# Switch.net
KiCad netlist of a schematic drawn in Altium Designer
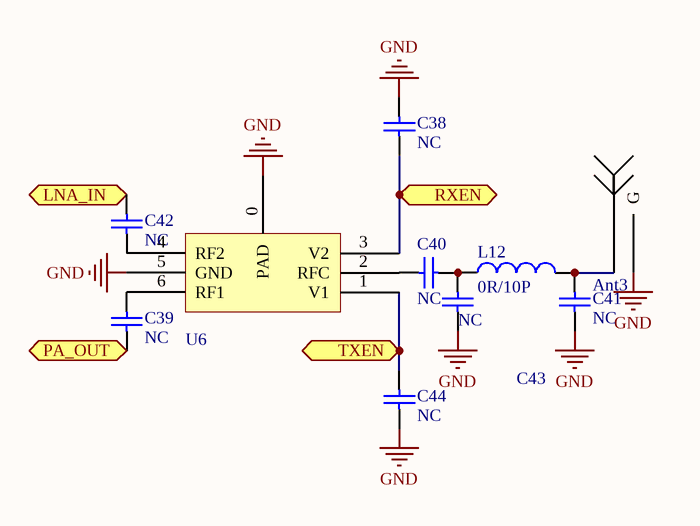
[diagram p0: Switch.SchDoc]

(export (version "E")
  (design (tool "Eeschema 10.0.6"))
  (components
    (comp (ref "Ant3") (value "Antenna") (footprint "SMA") (libsource (lib "RTC6705") (part "Antenna")))
    (comp (ref "C38")
      (value "NC")
      (footprint "0402")
      (description "Capacitor")
      (fields (field (name "Comment") "Cap") (field (name "PUBLISHER") "Altium Limited"))
      (libsource (lib "RTC6705") (part "Cap"))
    )
    (comp (ref "C39")
      (value "NC")
      (footprint "0402")
      (description "Capacitor")
      (fields (field (name "Comment") "Cap") (field (name "PUBLISHER") "Altium Limited"))
      (libsource (lib "RTC6705") (part "Cap"))
    )
    (comp (ref "C40")
      (value "NC")
      (footprint "0402")
      (description "Capacitor")
      (fields (field (name "Comment") "Cap") (field (name "PUBLISHER") "Altium Limited"))
      (libsource (lib "RTC6705") (part "Cap"))
    )
    (comp (ref "C41")
      (value "NC")
      (footprint "0402")
      (description "Capacitor")
      (fields (field (name "Comment") "Cap") (field (name "PUBLISHER") "Altium Limited"))
      (libsource (lib "RTC6705") (part "Cap"))
    )
    (comp (ref "C42")
      (value "NC")
      (footprint "0402")
      (description "Capacitor")
      (fields (field (name "Comment") "Cap") (field (name "PUBLISHER") "Altium Limited"))
      (libsource (lib "RTC6705") (part "Cap"))
    )
    (comp (ref "C43")
      (value "NC")
      (footprint "0402")
      (description "Capacitor")
      (fields (field (name "Comment") "Cap") (field (name "PUBLISHER") "Altium Limited"))
      (libsource (lib "RTC6705") (part "Cap"))
    )
    (comp (ref "C44")
      (value "NC")
      (footprint "0402")
      (description "Capacitor")
      (fields (field (name "Comment") "Cap") (field (name "PUBLISHER") "Altium Limited"))
      (libsource (lib "RTC6705") (part "Cap"))
    )
    (comp (ref "L12")
      (value "0R/10P")
      (footprint "0402")
      (description "Inductor")
      (fields (field (name "PUBLISHER") "Altium Limited"))
      (libsource (lib "Miscellaneous Devices") (part "Inductor"))
    )
    (comp (ref "U6")
      (value "SKY13370-374LF")
      (footprint "SKY65404-31")
      (libsource (lib "BK5811") (part "SKY13370-374LF"))
    )
  )
  (nets
    (net (code "1") (name "/LNA_IN") (class "Default")
      (node (ref "C42") (pin "2") (pinfunction "2_2") (pintype "passive"))
    )
    (net (code "2") (name "/PA_OUT") (class "Default")
      (node (ref "C39") (pin "1") (pinfunction "1_1") (pintype "passive"))
    )
    (net (code "3") (name "/RXEN") (class "Default")
      (node (ref "C38") (pin "2") (pinfunction "2_2") (pintype "passive"))
      (node (ref "U6") (pin "3") (pinfunction "V2_3") (pintype "passive"))
    )
    (net (code "4") (name "/TXEN") (class "Default")
      (node (ref "C44") (pin "2") (pinfunction "2_2") (pintype "passive"))
      (node (ref "U6") (pin "1") (pinfunction "V1_1") (pintype "passive"))
    )
    (net (code "5") (name "GND") (class "Default")
      (node (ref "Ant3") (pin "GND") (pinfunction "G_GND") (pintype "passive"))
      (node (ref "C38") (pin "1") (pinfunction "1_1") (pintype "passive"))
      (node (ref "C41") (pin "2") (pinfunction "2_2") (pintype "passive"))
      (node (ref "C43") (pin "2") (pinfunction "2_2") (pintype "passive"))
      (node (ref "C44") (pin "1") (pinfunction "1_1") (pintype "passive"))
      (node (ref "U6") (pin "0") (pinfunction "PAD_0") (pintype "passive"))
      (node (ref "U6") (pin "5") (pinfunction "GND_5") (pintype "passive"))
    )
    (net (code "6") (name "Net-(Ant3-Pad1)") (class "Default")
      (node (ref "Ant3") (pin "1") (pinfunction "1_1") (pintype "passive"))
      (node (ref "C41") (pin "1") (pinfunction "1_1") (pintype "passive"))
      (node (ref "L12") (pin "2") (pinfunction "2_2") (pintype "passive"))
    )
    (net (code "7") (name "Net-(C40-Pad2)") (class "Default")
      (node (ref "C40") (pin "2") (pinfunction "2_2") (pintype "passive"))
      (node (ref "C43") (pin "1") (pinfunction "1_1") (pintype "passive"))
      (node (ref "L12") (pin "1") (pinfunction "1_1") (pintype "passive"))
    )
    (net (code "8") (name "Net-(U6-RF1)") (class "Default")
      (node (ref "C39") (pin "2") (pinfunction "2_2") (pintype "passive"))
      (node (ref "U6") (pin "6") (pinfunction "RF1_6") (pintype "passive"))
    )
    (net (code "9") (name "Net-(U6-RF2)") (class "Default")
      (node (ref "C42") (pin "1") (pinfunction "1_1") (pintype "passive"))
      (node (ref "U6") (pin "4") (pinfunction "RF2_4") (pintype "passive"))
    )
    (net (code "10") (name "Net-(U6-RFC)") (class "Default")
      (node (ref "C40") (pin "1") (pinfunction "1_1") (pintype "passive"))
      (node (ref "U6") (pin "2") (pinfunction "RFC_2") (pintype "passive"))
    )
  )
)
